# power.net
KiCad netlist of a schematic drawn in Altium Designer
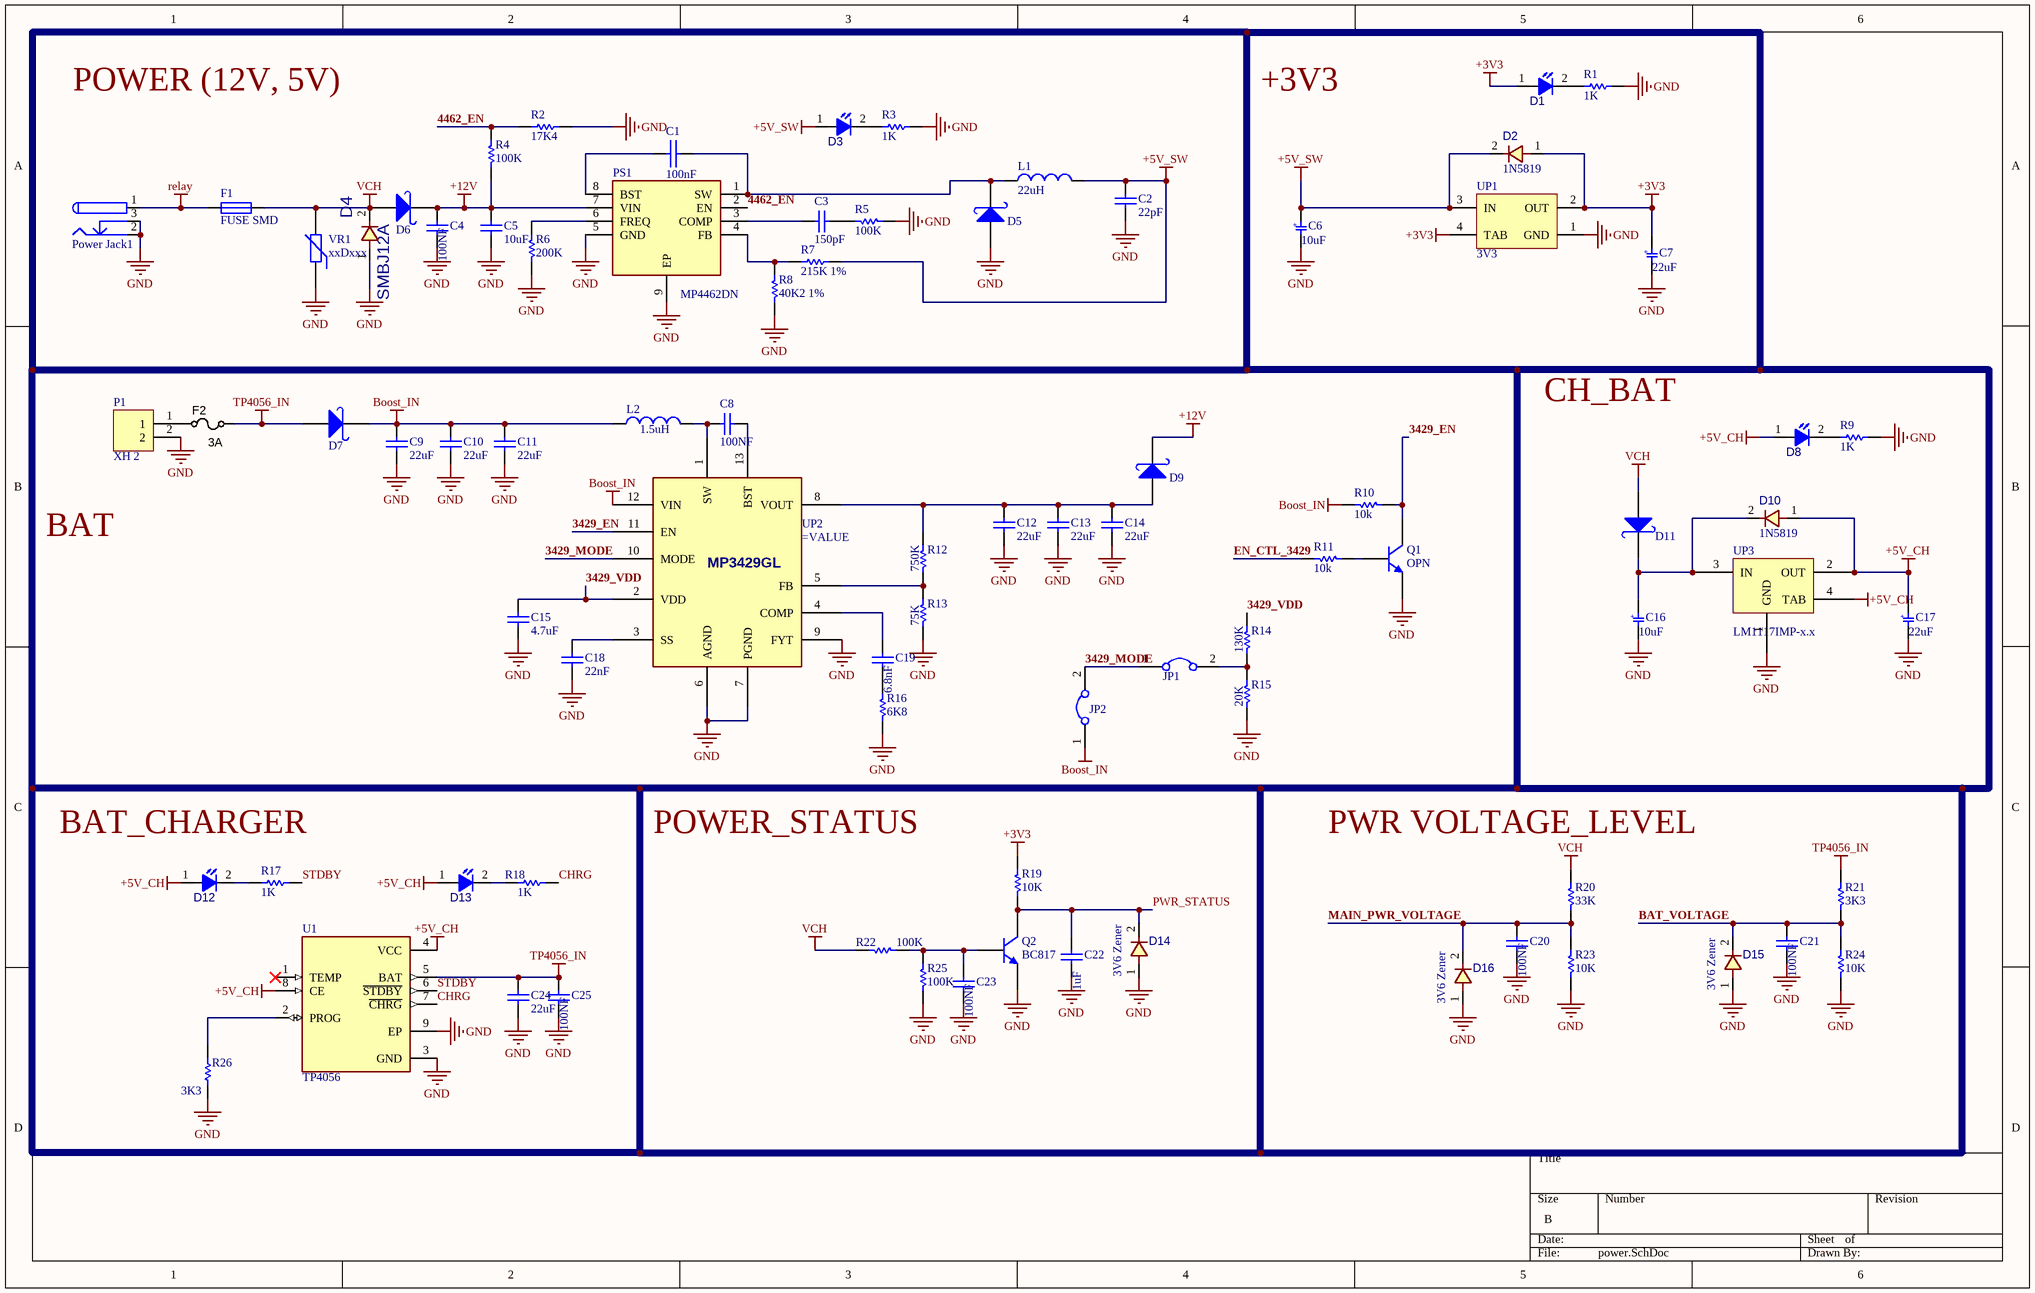
[diagram p0: power.SchDoc]

(export (version "E")
  (design (tool "Eeschema 10.0.6"))
  (components
    (comp (ref "C1")
      (value "100nF")
      (footprint "Cap-0805")
      (description "Capacitor")
      (fields (field (name "PUBLISHER") "Altium Limited"))
      (libsource (lib "altium-import") (part "root_1_Capacitor._"))
    )
    (comp (ref "C2")
      (value "22pF")
      (footprint "CAPC4817X12N")
      (description "CAP 1206")
      (fields (field (name "DESIGNER") "Abbas Basereh"))
      (libsource (lib "altium-import") (part "root_1_CAP SMD 1206_"))
    )
    (comp (ref "C3")
      (value "150pF")
      (footprint "CAPC3413X12N")
      (description "CAP 0805")
      (fields (field (name "DESIGNER") "Abbas Basereh"))
      (libsource (lib "altium-import") (part "root_0_CAP SMD 0805_"))
    )
    (comp (ref "C4")
      (value "100NF")
      (footprint "CAP0603")
      (description "TOTAL CAPACITOR SMD PACK")
      (fields (field (name "DESIGNER") "Abbas Basereh"))
      (libsource (lib "Altium") (part "CAP SMD PACKAGE"))
    )
    (comp (ref "C5")
      (value "10uF")
      (footprint "CAPC4817X12N")
      (description "CAP 1206")
      (fields (field (name "DESIGNER") "Abbas Basereh"))
      (libsource (lib "altium-import") (part "root_1_CAP SMD 1206_"))
    )
    (comp (ref "C6")
      (value "10uF")
      (footprint "Cap_A")
      (description "Capacitor Tantalum SMD")
      (libsource (lib "Capacitor") (part "Capacitor Tantalum SMD"))
    )
    (comp (ref "C7")
      (value "22uF")
      (footprint "Cap_A")
      (description "Capacitor Tantalum SMD")
      (libsource (lib "Capacitor") (part "Capacitor Tantalum SMD"))
    )
    (comp (ref "C8")
      (value "100NF")
      (footprint "CAP0603")
      (description "TOTAL CAPACITOR SMD PACK")
      (fields (field (name "DESIGNER") "Abbas Basereh"))
      (libsource (lib "Altium") (part "CAP SMD PACKAGE"))
    )
    (comp (ref "C9")
      (value "22uF")
      (footprint "Cap1206_(3216X15L)")
      (description "TOTAL CAPACITOR SMD PACK")
      (fields (field (name "DESIGNER") "Abbas Basereh"))
      (libsource (lib "Altium") (part "CAP SMD PACKAGE"))
    )
    (comp (ref "C10")
      (value "22uF")
      (footprint "Cap1206_(3216X15L)")
      (description "TOTAL CAPACITOR SMD PACK")
      (fields (field (name "DESIGNER") "Abbas Basereh"))
      (libsource (lib "Altium") (part "CAP SMD PACKAGE"))
    )
    (comp (ref "C11")
      (value "22uF")
      (footprint "Cap1206_(3216X15L)")
      (description "TOTAL CAPACITOR SMD PACK")
      (fields (field (name "DESIGNER") "Abbas Basereh"))
      (libsource (lib "Altium") (part "CAP SMD PACKAGE"))
    )
    (comp (ref "C12")
      (value "22uF")
      (footprint "Cap1206_(3216X15L)")
      (description "TOTAL CAPACITOR SMD PACK")
      (fields (field (name "DESIGNER") "Abbas Basereh"))
      (libsource (lib "Altium") (part "CAP SMD PACKAGE"))
    )
    (comp (ref "C13")
      (value "22uF")
      (footprint "Cap1206_(3216X15L)")
      (description "TOTAL CAPACITOR SMD PACK")
      (fields (field (name "DESIGNER") "Abbas Basereh"))
      (libsource (lib "Altium") (part "CAP SMD PACKAGE"))
    )
    (comp (ref "C14")
      (value "22uF")
      (footprint "Cap1206_(3216X15L)")
      (description "TOTAL CAPACITOR SMD PACK")
      (fields (field (name "DESIGNER") "Abbas Basereh"))
      (libsource (lib "Altium") (part "CAP SMD PACKAGE"))
    )
    (comp (ref "C15")
      (value "4.7uF")
      (footprint "CAPC3413X12N")
      (description "CAP 0805")
      (fields (field (name "DESIGNER") "Abbas Basereh"))
      (libsource (lib "2017AbbasBasereh9365731239 -ver1") (part "CAP SMD 0805"))
    )
    (comp (ref "C16")
      (value "10uF")
      (footprint "Cap_A")
      (description "Capacitor Tantalum SMD")
      (libsource (lib "Capacitor") (part "Capacitor Tantalum SMD"))
    )
    (comp (ref "C17")
      (value "22uF")
      (footprint "Cap_A")
      (description "Capacitor Tantalum SMD")
      (libsource (lib "Capacitor") (part "Capacitor Tantalum SMD"))
    )
    (comp (ref "C18")
      (value "22nF")
      (footprint "CAPC3413X12N")
      (description "CAP 0805")
      (fields (field (name "DESIGNER") "Abbas Basereh"))
      (libsource (lib "2017AbbasBasereh9365731239 -ver1") (part "CAP SMD 0805"))
    )
    (comp (ref "C19")
      (value "6.8nF")
      (footprint "CAP0603")
      (description "TOTAL CAPACITOR SMD PACK")
      (fields (field (name "DESIGNER") "Abbas Basereh"))
      (libsource (lib "Altium") (part "CAP SMD PACKAGE"))
    )
    (comp (ref "C20")
      (value "100NF")
      (footprint "CAP0603")
      (description "TOTAL CAPACITOR SMD PACK")
      (fields (field (name "DESIGNER") "Abbas Basereh"))
      (libsource (lib "Altium") (part "CAP SMD PACKAGE"))
    )
    (comp (ref "C21")
      (value "100NF")
      (footprint "CAP0603")
      (description "TOTAL CAPACITOR SMD PACK")
      (fields (field (name "DESIGNER") "Abbas Basereh"))
      (libsource (lib "Altium") (part "CAP SMD PACKAGE"))
    )
    (comp (ref "C22")
      (value "1uF")
      (footprint "CAP0603")
      (description "TOTAL CAPACITOR SMD PACK")
      (fields (field (name "DESIGNER") "Abbas Basereh"))
      (libsource (lib "Altium") (part "CAP SMD PACKAGE"))
    )
    (comp (ref "C23")
      (value "100NF")
      (footprint "CAP0603")
      (description "TOTAL CAPACITOR SMD PACK")
      (fields (field (name "DESIGNER") "Abbas Basereh"))
      (libsource (lib "Altium") (part "CAP SMD PACKAGE"))
    )
    (comp (ref "C24")
      (value "22uF")
      (footprint "Cap1206_(3216X15L)")
      (description "TOTAL CAPACITOR SMD PACK")
      (fields (field (name "DESIGNER") "Abbas Basereh"))
      (libsource (lib "Altium") (part "CAP SMD PACKAGE"))
    )
    (comp (ref "C25")
      (value "100NF")
      (footprint "CAP0603")
      (description "TOTAL CAPACITOR SMD PACK")
      (fields (field (name "DESIGNER") "Abbas Basereh"))
      (libsource (lib "Altium") (part "CAP SMD PACKAGE"))
    )
    (comp (ref "D1")
      (value "RED LED")
      (footprint "LED SMD 0805 (Red)")
      (description "LED SMD 0805")
      (libsource (lib "LED") (part "LED SMD 0805"))
    )
    (comp (ref "D2")
      (value "1N5819")
      (footprint "D_SMA")
      (description "DIODE, GENERAL PURPOSE, 1000V/1A")
      (fields (field (name "Comment") "1n5819 SMD SS31"))
      (libsource (lib "Diode") (part "1N4007 SMD M7"))
    )
    (comp (ref "D3")
      (value "RED LED")
      (footprint "LED SMD 0805 (Red)")
      (description "LED SMD 0805")
      (libsource (lib "LED") (part "LED SMD 0805"))
    )
    (comp (ref "D4")
      (value "SMBJ12A")
      (footprint "D_SMB")
      (description "TVS Surface Mount Transient Voltage Suppressors Diode")
      (fields (field (name "Comment") "SMBJ12A-TR SMD"))
      (libsource (lib "altium-import") (part "root_1_SMBJ12A-TR SMD_"))
    )
    (comp (ref "D5")
      (value "1n5822")
      (footprint "DIOM7568X24N")
      (description "Schottky Rectifiers")
      (fields
        (field (name "MANUFACTURER") "ON Semiconductor/Fairchild")
        (field (name "DESIGNER") "Abbas Basereh")
      )
      (libsource (lib "2017AbbasBasereh9365731239 -ver1") (part "1n5822 SMD"))
    )
    (comp (ref "D6")
      (value "1n5822")
      (footprint "DIOM7568X24N")
      (description "Schottky Rectifiers")
      (fields
        (field (name "MANUFACTURER") "ON Semiconductor/Fairchild")
        (field (name "DESIGNER") "Abbas Basereh")
      )
      (libsource (lib "2017AbbasBasereh9365731239 -ver1") (part "1n5822 SMD"))
    )
    (comp (ref "D7")
      (value "1n5822")
      (footprint "DIOM7568X24N")
      (description "Schottky Rectifiers")
      (fields
        (field (name "MANUFACTURER") "ON Semiconductor/Fairchild")
        (field (name "DESIGNER") "Abbas Basereh")
      )
      (libsource (lib "2017AbbasBasereh9365731239 -ver1") (part "1n5822 SMD"))
    )
    (comp (ref "D8")
      (value "RED LED")
      (footprint "LED SMD 0805 (Red)")
      (description "LED SMD 0805")
      (libsource (lib "LED") (part "LED SMD 0805"))
    )
    (comp (ref "D9")
      (value "1n5822")
      (footprint "DIOM7568X24N")
      (description "Schottky Rectifiers")
      (fields
        (field (name "MANUFACTURER") "ON Semiconductor/Fairchild")
        (field (name "DESIGNER") "Abbas Basereh")
      )
      (libsource (lib "2017AbbasBasereh9365731239 -ver1") (part "1n5822 SMD"))
    )
    (comp (ref "D10")
      (value "1N5819")
      (footprint "D_SMA")
      (description "DIODE, GENERAL PURPOSE, 1000V/1A")
      (fields (field (name "Comment") "1n5819 SMD SS31"))
      (libsource (lib "Diode") (part "1N4007 SMD M7"))
    )
    (comp (ref "D11")
      (value "1n5822")
      (footprint "DIOM7568X24N")
      (description "Schottky Rectifiers")
      (fields
        (field (name "MANUFACTURER") "ON Semiconductor/Fairchild")
        (field (name "DESIGNER") "Abbas Basereh")
      )
      (libsource (lib "2017AbbasBasereh9365731239 -ver1") (part "1n5822 SMD"))
    )
    (comp (ref "D12")
      (value "RED LED")
      (footprint "LED SMD 0805 (Red)")
      (description "LED SMD 0805")
      (libsource (lib "LED") (part "LED SMD 0805"))
    )
    (comp (ref "D13")
      (value "GREEN LED")
      (footprint "LED SMD 0805 (Green)")
      (description "LED SMD 0805")
      (libsource (lib "LED") (part "LED SMD 0805"))
    )
    (comp (ref "D14")
      (value "3V6 Zener")
      (footprint "D_SOD80")
      (description "DIODE, FAST SWTICHING, 0.3A, 0.5W")
      (fields (field (name "Comment") "5Z1"))
      (libsource (lib "Diode") (part "1N4148 SMD"))
    )
    (comp (ref "D15")
      (value "3V6 Zener")
      (footprint "D_SOD80")
      (description "DIODE, FAST SWTICHING, 0.3A, 0.5W")
      (fields (field (name "Comment") "5Z1"))
      (libsource (lib "Diode") (part "1N4148 SMD"))
    )
    (comp (ref "D16")
      (value "3V6 Zener")
      (footprint "D_SOD80")
      (description "DIODE, FAST SWTICHING, 0.3A, 0.5W")
      (fields (field (name "Comment") "5Z1"))
      (libsource (lib "Diode") (part "1N4148 SMD"))
    )
    (comp (ref "F1")
      (value "FUSE SMD")
      (footprint "8-1206")
      (description "SMD FUSE")
      (libsource (lib "altium-import") (part "root_0_FUSE SMD_"))
    )
    (comp (ref "F2")
      (value "3A")
      (footprint "RESC1608X55N")
      (description "Fuse 3A 63VDC 0603 SMD")
      (libsource (lib "altium-import") (part "root_0_FUSE_160mA_0603_"))
    )
    (comp (ref "JP1")
      (value "Jumper")
      (footprint "Jumper Small - 2.54 - GRAY")
      (libsource (lib "altium-import") (part "root_0_Jumper_"))
    )
    (comp (ref "JP2")
      (value "Jumper")
      (footprint "Jumper Small - 2.54 - GRAY")
      (libsource (lib "altium-import") (part "root_1_Jumper_"))
    )
    (comp (ref "L1")
      (value "22uH")
      (footprint "INDUCTOR_SMD_3A")
      (libsource (lib "AMINLIB") (part "INDUCTOR_SMD_3A"))
    )
    (comp (ref "L2")
      (value "1.5uH")
      (footprint "INDUCTOR_SMD_3A")
      (libsource (lib "AMINLIB") (part "INDUCTOR_SMD_3A"))
    )
    (comp (ref "P1")
      (value "XH 2")
      (footprint "XH 2 PIN ( White )")
      (description "Conector XH 2 Pin")
      (libsource (lib "altium-import") (part "root_1_Conector XH 2 Pin_"))
    )
    (comp (ref "Power Jack1")
      (value "Power Jack.")
      (footprint "Power Jack.")
      (libsource (lib "A.Mohebbi") (part "Power Jack."))
    )
    (comp (ref "PS1")
      (value "MP4462DN")
      (footprint "SOIC127P600X170-9N")
      (description "Power Supply")
      (libsource (lib "*") (part "MP4560DN-LF"))
    )
    (comp (ref "Q1")
      (value "OPN")
      (footprint "SOT23_N")
      (description "NPN Silicon Epitaxial Planar Transistor")
      (fields (field (name "PUBLISHER") "Abbas Basereh"))
      (libsource (lib "2017AbbasBasereh9365731239 -ver1") (part "C945"))
    )
    (comp (ref "Q2")
      (value "BC817")
      (footprint "SOT23_N")
      (description "NPN Silicon Epitaxial Planar Transistor")
      (fields (field (name "PUBLISHER") "Abbas Basereh"))
      (libsource (lib "2017AbbasBasereh9365731239 -ver1") (part "C945"))
    )
    (comp (ref "R1")
      (value "1K")
      (footprint "R0603")
      (description "Resistor SMD 0603")
      (libsource (lib "Resistor") (part "Resistor SMD 0603"))
    )
    (comp (ref "R2")
      (value "17K4")
      (footprint "SMD-0805-RES")
      (description "Resistor SMD 0805")
      (libsource (lib "Resistor") (part "Resistor SMD 0805"))
    )
    (comp (ref "R3")
      (value "1K")
      (footprint "R0603")
      (description "Resistor SMD 0603")
      (libsource (lib "Resistor") (part "Resistor SMD 0603"))
    )
    (comp (ref "R4")
      (value "100K")
      (footprint "R0603")
      (description "Resistor SMD 0603")
      (libsource (lib "Resistor") (part "Resistor SMD 0603"))
    )
    (comp (ref "R5")
      (value "100K")
      (footprint "R0603")
      (description "Resistor SMD 0603")
      (libsource (lib "Resistor") (part "Resistor SMD 0603"))
    )
    (comp (ref "R6")
      (value "200K")
      (footprint "R0603")
      (libsource (lib "Resistor") (part "Resistor SMD 0603"))
    )
    (comp (ref "R7")
      (value "215K 1%")
      (footprint "SMD-0805-RES")
      (description "Resistor SMD 0805")
      (libsource (lib "Resistor") (part "Resistor SMD 0805"))
    )
    (comp (ref "R8")
      (value "40K2 1%")
      (footprint "R0603")
      (description "Resistor SMD 0603")
      (fields (field (name "Comment") "40K2"))
      (libsource (lib "Resistor") (part "Resistor SMD 0603"))
    )
    (comp (ref "R9")
      (value "1K")
      (footprint "R0603")
      (description "Resistor SMD 0603")
      (libsource (lib "Resistor") (part "Resistor SMD 0603"))
    )
    (comp (ref "R10")
      (value "10k")
      (footprint "R0603")
      (description "Resistor SMD 0603")
      (libsource (lib "Resistor") (part "Resistor SMD 0603"))
    )
    (comp (ref "R11")
      (value "10k")
      (footprint "R0603")
      (description "Resistor SMD 0603")
      (libsource (lib "Resistor") (part "Resistor SMD 0603"))
    )
    (comp (ref "R12")
      (value "750K")
      (footprint "R0603")
      (description "Resistor SMD 0603")
      (libsource (lib "Resistor") (part "Resistor SMD 0603"))
    )
    (comp (ref "R13")
      (value "75K")
      (footprint "R0603")
      (description "Resistor SMD 0603")
      (libsource (lib "Resistor") (part "Resistor SMD 0603"))
    )
    (comp (ref "R14")
      (value "130K")
      (footprint "R0603")
      (description "Resistor SMD 0603")
      (libsource (lib "Resistor") (part "Resistor SMD 0603"))
    )
    (comp (ref "R15")
      (value "20K")
      (footprint "R0603")
      (description "Resistor SMD 0603")
      (libsource (lib "Resistor") (part "Resistor SMD 0603"))
    )
    (comp (ref "R16")
      (value "6K8")
      (footprint "R0603")
      (description "Resistor SMD 0603")
      (fields (field (name "Comment") "100K"))
      (libsource (lib "Resistor") (part "Resistor SMD 0603"))
    )
    (comp (ref "R17")
      (value "1K")
      (footprint "R0603")
      (description "Resistor SMD 0603")
      (libsource (lib "Resistor") (part "Resistor SMD 0603"))
    )
    (comp (ref "R18")
      (value "1K")
      (footprint "R0603")
      (description "Resistor SMD 0603")
      (libsource (lib "Resistor") (part "Resistor SMD 0603"))
    )
    (comp (ref "R19")
      (value "10K")
      (footprint "R0603")
      (description "Resistor SMD 0603")
      (libsource (lib "Resistor") (part "Resistor SMD 0603"))
    )
    (comp (ref "R20")
      (value "33K")
      (footprint "R0603")
      (description "Resistor SMD 0603")
      (libsource (lib "Resistor") (part "Resistor SMD 0603"))
    )
    (comp (ref "R21")
      (value "3K3")
      (footprint "R0603")
      (description "Resistor SMD 0603")
      (libsource (lib "Resistor") (part "Resistor SMD 0603"))
    )
    (comp (ref "R22")
      (value "100K")
      (footprint "R0603")
      (description "Resistor SMD 0603")
      (libsource (lib "Resistor") (part "Resistor SMD 0603"))
    )
    (comp (ref "R23")
      (value "10K")
      (footprint "R0603")
      (description "Resistor SMD 0603")
      (libsource (lib "Resistor") (part "Resistor SMD 0603"))
    )
    (comp (ref "R24")
      (value "10K")
      (footprint "R0603")
      (description "Resistor SMD 0603")
      (libsource (lib "Resistor") (part "Resistor SMD 0603"))
    )
    (comp (ref "R25")
      (value "100K")
      (footprint "R0603")
      (description "Resistor SMD 0603")
      (libsource (lib "Resistor") (part "Resistor SMD 0603"))
    )
    (comp (ref "R26")
      (value "3K3")
      (footprint "R0603")
      (description "Resistor SMD 0603")
      (libsource (lib "Resistor") (part "Resistor SMD 0603"))
    )
    (comp (ref "U1")
      (value "TP4056")
      (footprint "SOP127P600X175-9N")
      (description "Complete single cell Li-Ion battery with a constant current / constant voltage linear charger")
      (fields (field (name "MF") "NanJing Top Power ASIC Corp."))
      (libsource (lib "TP4056") (part "TP4056"))
    )
    (comp (ref "UP1")
      (value "3V3")
      (footprint "SOT223")
      (description "x.x Volt, 800mA Low-Dropout Linear Regulator, 4-pin SOT-223")
      (fields (field (name "DESIGNER") "Ali Hafizi"))
      (libsource (lib "altium-import") (part "root_0_AMS1117-x.x_"))
    )
    (comp (ref "UP2")
      (value "~")
      (footprint "GFN-13 (3mm*4mm)")
      (description "16VOUT, 21A, High-Efficiency,  Fully Integrated, Synchronous,  Boost Converter")
      (libsource (lib "MP3429GL") (part "MP3429"))
    )
    (comp (ref "UP3")
      (value "LM1117IMP-x.x")
      (footprint "SOT223_4")
      (description "x.x Volt, 800mA Low-Dropout Linear Regulator, 4-pin SOT-223")
      (fields (field (name "DESIGNER") "Abbas Basereh"))
      (libsource (lib "altium-import") (part "root_0_LM1117IMP-x.x_"))
    )
    (comp (ref "VR1")
      (value "xxDxxx")
      (footprint "05D XXX")
      (description "VARISTORS")
      (fields
        (field (name "MANUFACTURER") "china-canada-philipina")
        (field (name "DESIGNER") "Abbas Basereh")
        (field (name "PUBLISHER") "ABBAS BASEREH")
      )
      (libsource (lib "2017AbbasBasereh9365731239 -ver1") (part "VARISTOR (VDR)"))
    )
  )
  (nets
    (net (code "1") (name "+3V3") (class "Default")
      (node (ref "C7") (pin "2") (pinfunction "2_2") (pintype "passive"))
      (node (ref "D1") (pin "1") (pinfunction "ANODE_1") (pintype "passive"))
      (node (ref "D2") (pin "1") (pinfunction "1_1") (pintype "passive"))
      (node (ref "R19") (pin "1") (pinfunction "1_1") (pintype "passive"))
      (node (ref "UP1") (pin "2") (pinfunction "OUT_2") (pintype "power_in"))
      (node (ref "UP1") (pin "4") (pinfunction "TAB_4") (pintype "power_in"))
    )
    (net (code "2") (name "+5V_CH") (class "Default")
      (node (ref "C17") (pin "2") (pinfunction "2_2") (pintype "passive"))
      (node (ref "D10") (pin "1") (pinfunction "1_1") (pintype "passive"))
      (node (ref "D12") (pin "1") (pinfunction "ANODE_1") (pintype "passive"))
      (node (ref "D13") (pin "1") (pinfunction "ANODE_1") (pintype "passive"))
      (node (ref "D8") (pin "1") (pinfunction "ANODE_1") (pintype "passive"))
      (node (ref "U1") (pin "4") (pinfunction "VCC_4") (pintype "power_in"))
      (node (ref "U1") (pin "8") (pinfunction "CE_8") (pintype "input"))
      (node (ref "UP3") (pin "2") (pinfunction "OUT_2") (pintype "power_in"))
      (node (ref "UP3") (pin "4") (pinfunction "TAB_4") (pintype "power_in"))
    )
    (net (code "3") (name "+5V_SW") (class "Default")
      (node (ref "C2") (pin "2") (pinfunction "2_2") (pintype "passive"))
      (node (ref "C6") (pin "2") (pinfunction "2_2") (pintype "passive"))
      (node (ref "D2") (pin "2") (pinfunction "2_2") (pintype "passive"))
      (node (ref "D3") (pin "1") (pinfunction "ANODE_1") (pintype "passive"))
      (node (ref "L1") (pin "2") (pinfunction "2_2") (pintype "passive"))
      (node (ref "R7") (pin "2") (pinfunction "2_2") (pintype "passive"))
      (node (ref "UP1") (pin "3") (pinfunction "IN_3") (pintype "power_in"))
    )
    (net (code "4") (name "+12V") (class "Default")
      (node (ref "C4") (pin "2") (pinfunction "2_2") (pintype "passive"))
      (node (ref "C5") (pin "2") (pinfunction "2_2") (pintype "passive"))
      (node (ref "D6") (pin "2") (pinfunction "K_2") (pintype "passive"))
      (node (ref "D9") (pin "2") (pinfunction "K_2") (pintype "passive"))
      (node (ref "PS1") (pin "7") (pinfunction "VIN_7") (pintype "passive"))
      (node (ref "R4") (pin "1") (pinfunction "1_1") (pintype "passive"))
    )
    (net (code "5") (name "/3429_EN") (class "Default")
      (node (ref "Q1") (pin "3") (pinfunction "C_3") (pintype "passive"))
      (node (ref "R10") (pin "2") (pinfunction "2_2") (pintype "passive"))
      (node (ref "UP2") (pin "11") (pinfunction "EN_11") (pintype "passive"))
    )
    (net (code "6") (name "/3429_MODE") (class "Default")
      (node (ref "JP1") (pin "1") (pinfunction "1_1") (pintype "passive"))
      (node (ref "JP2") (pin "2") (pinfunction "2_2") (pintype "passive"))
      (node (ref "UP2") (pin "10") (pinfunction "MODE_10") (pintype "passive"))
    )
    (net (code "7") (name "/3429_VDD") (class "Default")
      (node (ref "C15") (pin "2") (pinfunction "2_2") (pintype "passive"))
      (node (ref "R14") (pin "2") (pinfunction "2_2") (pintype "passive"))
      (node (ref "UP2") (pin "2") (pinfunction "VDD_2") (pintype "passive"))
    )
    (net (code "8") (name "/4462_EN") (class "Default")
      (node (ref "PS1") (pin "2") (pinfunction "EN_2") (pintype "passive"))
      (node (ref "R2") (pin "1") (pinfunction "1_1") (pintype "passive"))
      (node (ref "R4") (pin "2") (pinfunction "2_2") (pintype "passive"))
    )
    (net (code "10") (name "/BAT_VOLTAGE") (class "Default")
      (node (ref "C21") (pin "2") (pinfunction "2_2") (pintype "passive"))
      (node (ref "D15") (pin "2") (pinfunction "2_2") (pintype "passive"))
      (node (ref "R21") (pin "2") (pinfunction "2_2") (pintype "passive"))
      (node (ref "R24") (pin "1") (pinfunction "1_1") (pintype "passive"))
    )
    (net (code "11") (name "/CHRG") (class "Default")
      (node (ref "R18") (pin "2") (pinfunction "2_2") (pintype "passive"))
      (node (ref "U1") (pin "7") (pinfunction "~{CHRG}_7") (pintype "output"))
    )
    (net (code "12") (name "/EN_CTL_3429") (class "Default")
      (node (ref "R11") (pin "2") (pinfunction "2_2") (pintype "passive"))
    )
    (net (code "13") (name "/MAIN_PWR_VOLTAGE") (class "Default")
      (node (ref "C20") (pin "2") (pinfunction "2_2") (pintype "passive"))
      (node (ref "D16") (pin "2") (pinfunction "2_2") (pintype "passive"))
      (node (ref "R20") (pin "2") (pinfunction "2_2") (pintype "passive"))
      (node (ref "R23") (pin "1") (pinfunction "1_1") (pintype "passive"))
    )
    (net (code "14") (name "/PWR_STATUS") (class "Default")
      (node (ref "C22") (pin "2") (pinfunction "2_2") (pintype "passive"))
      (node (ref "D14") (pin "2") (pinfunction "2_2") (pintype "passive"))
      (node (ref "Q2") (pin "3") (pinfunction "C_3") (pintype "passive"))
      (node (ref "R19") (pin "2") (pinfunction "2_2") (pintype "passive"))
    )
    (net (code "15") (name "/STDBY") (class "Default")
      (node (ref "R17") (pin "2") (pinfunction "2_2") (pintype "passive"))
      (node (ref "U1") (pin "6") (pinfunction "~{STDBY}_6") (pintype "output"))
    )
    (net (code "16") (name "Boost_IN") (class "Default")
      (node (ref "C10") (pin "2") (pinfunction "2_2") (pintype "passive"))
      (node (ref "C11") (pin "2") (pinfunction "2_2") (pintype "passive"))
      (node (ref "C9") (pin "2") (pinfunction "2_2") (pintype "passive"))
      (node (ref "D7") (pin "2") (pinfunction "K_2") (pintype "passive"))
      (node (ref "JP2") (pin "1") (pinfunction "1_1") (pintype "passive"))
      (node (ref "L2") (pin "1") (pinfunction "1_1") (pintype "passive"))
      (node (ref "R10") (pin "1") (pinfunction "1_1") (pintype "passive"))
      (node (ref "UP2") (pin "12") (pinfunction "VIN_12") (pintype "passive"))
    )
    (net (code "17") (name "GND") (class "Default")
      (node (ref "C10") (pin "1") (pinfunction "1_1") (pintype "passive"))
      (node (ref "C11") (pin "1") (pinfunction "1_1") (pintype "passive"))
      (node (ref "C12") (pin "1") (pinfunction "1_1") (pintype "passive"))
      (node (ref "C13") (pin "1") (pinfunction "1_1") (pintype "passive"))
      (node (ref "C14") (pin "1") (pinfunction "1_1") (pintype "passive"))
      (node (ref "C15") (pin "1") (pinfunction "1_1") (pintype "passive"))
      (node (ref "C16") (pin "1") (pinfunction "1_1") (pintype "passive"))
      (node (ref "C17") (pin "1") (pinfunction "1_1") (pintype "passive"))
      (node (ref "C18") (pin "1") (pinfunction "1_1") (pintype "passive"))
      (node (ref "C2") (pin "1") (pinfunction "1_1") (pintype "passive"))
      (node (ref "C20") (pin "1") (pinfunction "1_1") (pintype "passive"))
      (node (ref "C21") (pin "1") (pinfunction "1_1") (pintype "passive"))
      (node (ref "C22") (pin "1") (pinfunction "1_1") (pintype "passive"))
      (node (ref "C23") (pin "1") (pinfunction "1_1") (pintype "passive"))
      (node (ref "C24") (pin "1") (pinfunction "1_1") (pintype "passive"))
      (node (ref "C25") (pin "1") (pinfunction "1_1") (pintype "passive"))
      (node (ref "C4") (pin "1") (pinfunction "1_1") (pintype "passive"))
      (node (ref "C5") (pin "1") (pinfunction "1_1") (pintype "passive"))
      (node (ref "C6") (pin "1") (pinfunction "1_1") (pintype "passive"))
      (node (ref "C7") (pin "1") (pinfunction "1_1") (pintype "passive"))
      (node (ref "C9") (pin "1") (pinfunction "1_1") (pintype "passive"))
      (node (ref "D14") (pin "1") (pinfunction "1_1") (pintype "passive"))
      (node (ref "D15") (pin "1") (pinfunction "1_1") (pintype "passive"))
      (node (ref "D16") (pin "1") (pinfunction "1_1") (pintype "passive"))
      (node (ref "D4") (pin "1") (pinfunction "1_1") (pintype "passive"))
      (node (ref "D5") (pin "1") (pinfunction "A_1") (pintype "passive"))
      (node (ref "P1") (pin "2") (pinfunction "2_2") (pintype "passive"))
      (node (ref "PS1") (pin "5") (pinfunction "GND_5") (pintype "passive"))
      (node (ref "PS1") (pin "9") (pinfunction "EP_9") (pintype "passive"))
      (node (ref "Power Jack1") (pin "2") (pinfunction "2_2") (pintype "power_in"))
      (node (ref "Power Jack1") (pin "3") (pinfunction "3_3") (pintype "power_in"))
      (node (ref "Q1") (pin "2") (pinfunction "E_2") (pintype "passive"))
      (node (ref "Q2") (pin "2") (pinfunction "E_2") (pintype "passive"))
      (node (ref "R1") (pin "2") (pinfunction "2_2") (pintype "passive"))
      (node (ref "R13") (pin "1") (pinfunction "1_1") (pintype "passive"))
      (node (ref "R15") (pin "1") (pinfunction "1_1") (pintype "passive"))
      (node (ref "R16") (pin "2") (pinfunction "2_2") (pintype "passive"))
      (node (ref "R2") (pin "2") (pinfunction "2_2") (pintype "passive"))
      (node (ref "R23") (pin "2") (pinfunction "2_2") (pintype "passive"))
      (node (ref "R24") (pin "2") (pinfunction "2_2") (pintype "passive"))
      (node (ref "R25") (pin "2") (pinfunction "2_2") (pintype "passive"))
      (node (ref "R26") (pin "1") (pinfunction "1_1") (pintype "passive"))
      (node (ref "R3") (pin "2") (pinfunction "2_2") (pintype "passive"))
      (node (ref "R5") (pin "2") (pinfunction "2_2") (pintype "passive"))
      (node (ref "R6") (pin "2") (pinfunction "2_2") (pintype "passive"))
      (node (ref "R8") (pin "1") (pinfunction "1_1") (pintype "passive"))
      (node (ref "R9") (pin "2") (pinfunction "2_2") (pintype "passive"))
      (node (ref "U1") (pin "3") (pinfunction "GND_3") (pintype "power_in"))
      (node (ref "U1") (pin "9") (pinfunction "EP_9") (pintype "passive"))
      (node (ref "UP1") (pin "1") (pinfunction "GND_1") (pintype "power_in"))
      (node (ref "UP2") (pin "6") (pinfunction "AGND_6") (pintype "passive"))
      (node (ref "UP2") (pin "7") (pinfunction "PGND_7") (pintype "passive"))
      (node (ref "UP2") (pin "9") (pinfunction "FYT_9") (pintype "passive"))
      (node (ref "UP3") (pin "1") (pinfunction "GND_1") (pintype "power_in"))
      (node (ref "VR1") (pin "1") (pinfunction "1_1") (pintype "passive"))
    )
    (net (code "18") (name "Net-(C3-Pad2)") (class "Default")
      (node (ref "C3") (pin "2") (pinfunction "2_2") (pintype "passive"))
      (node (ref "R5") (pin "1") (pinfunction "1_1") (pintype "passive"))
    )
    (net (code "19") (name "Net-(C19-Pad1)") (class "Default")
      (node (ref "C19") (pin "1") (pinfunction "1_1") (pintype "passive"))
      (node (ref "R16") (pin "1") (pinfunction "1_1") (pintype "passive"))
    )
    (net (code "20") (name "Net-(D1-CATHODE)") (class "Default")
      (node (ref "D1") (pin "2") (pinfunction "CATHODE_2") (pintype "passive"))
      (node (ref "R1") (pin "1") (pinfunction "1_1") (pintype "passive"))
    )
    (net (code "21") (name "Net-(D3-CATHODE)") (class "Default")
      (node (ref "D3") (pin "2") (pinfunction "CATHODE_2") (pintype "passive"))
      (node (ref "R3") (pin "1") (pinfunction "1_1") (pintype "passive"))
    )
    (net (code "22") (name "Net-(D5-K)") (class "Default")
      (node (ref "C1") (pin "2") (pinfunction "2_2") (pintype "passive"))
      (node (ref "D5") (pin "2") (pinfunction "K_2") (pintype "passive"))
      (node (ref "L1") (pin "1") (pinfunction "1_1") (pintype "passive"))
      (node (ref "PS1") (pin "1") (pinfunction "SW_1") (pintype "passive"))
    )
    (net (code "23") (name "Net-(D8-CATHODE)") (class "Default")
      (node (ref "D8") (pin "2") (pinfunction "CATHODE_2") (pintype "passive"))
      (node (ref "R9") (pin "1") (pinfunction "1_1") (pintype "passive"))
    )
    (net (code "24") (name "Net-(D9-A)") (class "Default")
      (node (ref "C12") (pin "2") (pinfunction "2_2") (pintype "passive"))
      (node (ref "C13") (pin "2") (pinfunction "2_2") (pintype "passive"))
      (node (ref "C14") (pin "2") (pinfunction "2_2") (pintype "passive"))
      (node (ref "D9") (pin "1") (pinfunction "A_1") (pintype "passive"))
      (node (ref "R12") (pin "2") (pinfunction "2_2") (pintype "passive"))
      (node (ref "UP2") (pin "8") (pinfunction "VOUT_8") (pintype "passive"))
    )
    (net (code "25") (name "Net-(D11-K)") (class "Default")
      (node (ref "C16") (pin "2") (pinfunction "2_2") (pintype "passive"))
      (node (ref "D10") (pin "2") (pinfunction "2_2") (pintype "passive"))
      (node (ref "D11") (pin "2") (pinfunction "K_2") (pintype "passive"))
      (node (ref "UP3") (pin "3") (pinfunction "IN_3") (pintype "power_in"))
    )
    (net (code "26") (name "Net-(D12-CATHODE)") (class "Default")
      (node (ref "D12") (pin "2") (pinfunction "CATHODE_2") (pintype "passive"))
      (node (ref "R17") (pin "1") (pinfunction "1_1") (pintype "passive"))
    )
    (net (code "27") (name "Net-(D13-CATHODE)") (class "Default")
      (node (ref "D13") (pin "2") (pinfunction "CATHODE_2") (pintype "passive"))
      (node (ref "R18") (pin "1") (pinfunction "1_1") (pintype "passive"))
    )
    (net (code "28") (name "Net-(F2-Pad1)") (class "Default")
      (node (ref "F2") (pin "1") (pinfunction "1_1") (pintype "passive"))
      (node (ref "P1") (pin "1") (pinfunction "1_1") (pintype "passive"))
    )
    (net (code "29") (name "Net-(JP1-Pad2)") (class "Default")
      (node (ref "JP1") (pin "2") (pinfunction "2_2") (pintype "passive"))
      (node (ref "R14") (pin "1") (pinfunction "1_1") (pintype "passive"))
      (node (ref "R15") (pin "2") (pinfunction "2_2") (pintype "passive"))
    )
    (net (code "30") (name "Net-(PS1-BST)") (class "Default")
      (node (ref "C1") (pin "1") (pinfunction "1_1") (pintype "passive"))
      (node (ref "PS1") (pin "8") (pinfunction "BST_8") (pintype "passive"))
    )
    (net (code "31") (name "Net-(PS1-COMP)") (class "Default")
      (node (ref "C3") (pin "1") (pinfunction "1_1") (pintype "passive"))
      (node (ref "PS1") (pin "3") (pinfunction "COMP_3") (pintype "passive"))
    )
    (net (code "32") (name "Net-(PS1-FB)") (class "Default")
      (node (ref "PS1") (pin "4") (pinfunction "FB_4") (pintype "passive"))
      (node (ref "R7") (pin "1") (pinfunction "1_1") (pintype "passive"))
      (node (ref "R8") (pin "2") (pinfunction "2_2") (pintype "passive"))
    )
    (net (code "33") (name "Net-(PS1-FREQ)") (class "Default")
      (node (ref "PS1") (pin "6") (pinfunction "FREQ_6") (pintype "passive"))
      (node (ref "R6") (pin "1") (pinfunction "1_1") (pintype "passive"))
    )
    (net (code "34") (name "Net-(Q1-B)") (class "Default")
      (node (ref "Q1") (pin "1") (pinfunction "B_1") (pintype "passive"))
      (node (ref "R11") (pin "1") (pinfunction "1_1") (pintype "passive"))
    )
    (net (code "35") (name "Net-(Q2-B)") (class "Default")
      (node (ref "C23") (pin "2") (pinfunction "2_2") (pintype "passive"))
      (node (ref "Q2") (pin "1") (pinfunction "B_1") (pintype "passive"))
      (node (ref "R22") (pin "1") (pinfunction "1_1") (pintype "passive"))
      (node (ref "R25") (pin "1") (pinfunction "1_1") (pintype "passive"))
    )
    (net (code "36") (name "Net-(U1-PROG)") (class "Default")
      (node (ref "R26") (pin "2") (pinfunction "2_2") (pintype "passive"))
      (node (ref "U1") (pin "2") (pinfunction "PROG_2") (pintype "bidirectional"))
    )
    (net (code "37") (name "Net-(UP2-BST)") (class "Default")
      (node (ref "C8") (pin "2") (pinfunction "2_2") (pintype "passive"))
      (node (ref "UP2") (pin "13") (pinfunction "BST_13") (pintype "passive"))
    )
    (net (code "38") (name "Net-(UP2-COMP)") (class "Default")
      (node (ref "C19") (pin "2") (pinfunction "2_2") (pintype "passive"))
      (node (ref "UP2") (pin "4") (pinfunction "COMP_4") (pintype "passive"))
    )
    (net (code "39") (name "Net-(UP2-FB)") (class "Default")
      (node (ref "R12") (pin "1") (pinfunction "1_1") (pintype "passive"))
      (node (ref "R13") (pin "2") (pinfunction "2_2") (pintype "passive"))
      (node (ref "UP2") (pin "5") (pinfunction "FB_5") (pintype "passive"))
    )
    (net (code "40") (name "Net-(UP2-SS)") (class "Default")
      (node (ref "C18") (pin "2") (pinfunction "2_2") (pintype "passive"))
      (node (ref "UP2") (pin "3") (pinfunction "SS_3") (pintype "passive"))
    )
    (net (code "41") (name "Net-(UP2-SW)") (class "Default")
      (node (ref "C8") (pin "1") (pinfunction "1_1") (pintype "passive"))
      (node (ref "L2") (pin "2") (pinfunction "2_2") (pintype "passive"))
      (node (ref "UP2") (pin "1") (pinfunction "SW_1") (pintype "passive"))
    )
    (net (code "42") (name "TP4056_IN") (class "Default")
      (node (ref "C24") (pin "2") (pinfunction "2_2") (pintype "passive"))
      (node (ref "C25") (pin "2") (pinfunction "2_2") (pintype "passive"))
      (node (ref "D7") (pin "1") (pinfunction "A_1") (pintype "passive"))
      (node (ref "F2") (pin "2") (pinfunction "2_2") (pintype "passive"))
      (node (ref "R21") (pin "1") (pinfunction "1_1") (pintype "passive"))
      (node (ref "U1") (pin "5") (pinfunction "BAT_5") (pintype "output"))
    )
    (net (code "43") (name "VCH") (class "Default")
      (node (ref "D11") (pin "1") (pinfunction "A_1") (pintype "passive"))
      (node (ref "D4") (pin "2") (pinfunction "2_2") (pintype "passive"))
      (node (ref "D6") (pin "1") (pinfunction "A_1") (pintype "passive"))
      (node (ref "F1") (pin "2") (pinfunction "2_2") (pintype "passive"))
      (node (ref "R20") (pin "1") (pinfunction "1_1") (pintype "passive"))
      (node (ref "R22") (pin "2") (pinfunction "2_2") (pintype "passive"))
      (node (ref "VR1") (pin "2") (pinfunction "2_2") (pintype "passive"))
    )
    (net (code "44") (name "relay") (class "Default")
      (node (ref "F1") (pin "1") (pinfunction "1_1") (pintype "passive"))
      (node (ref "Power Jack1") (pin "1") (pinfunction "1_1") (pintype "power_in"))
    )
    (net (code "45") (name "unconnected-(U1-TEMP-Pad1)") (class "Default")
      (node (ref "U1") (pin "1") (pinfunction "TEMP_1") (pintype "input+no_connect"))
    )
  )
)
